# Prototipo_1_2.net
KiCad netlist of a schematic drawn in EAGLE
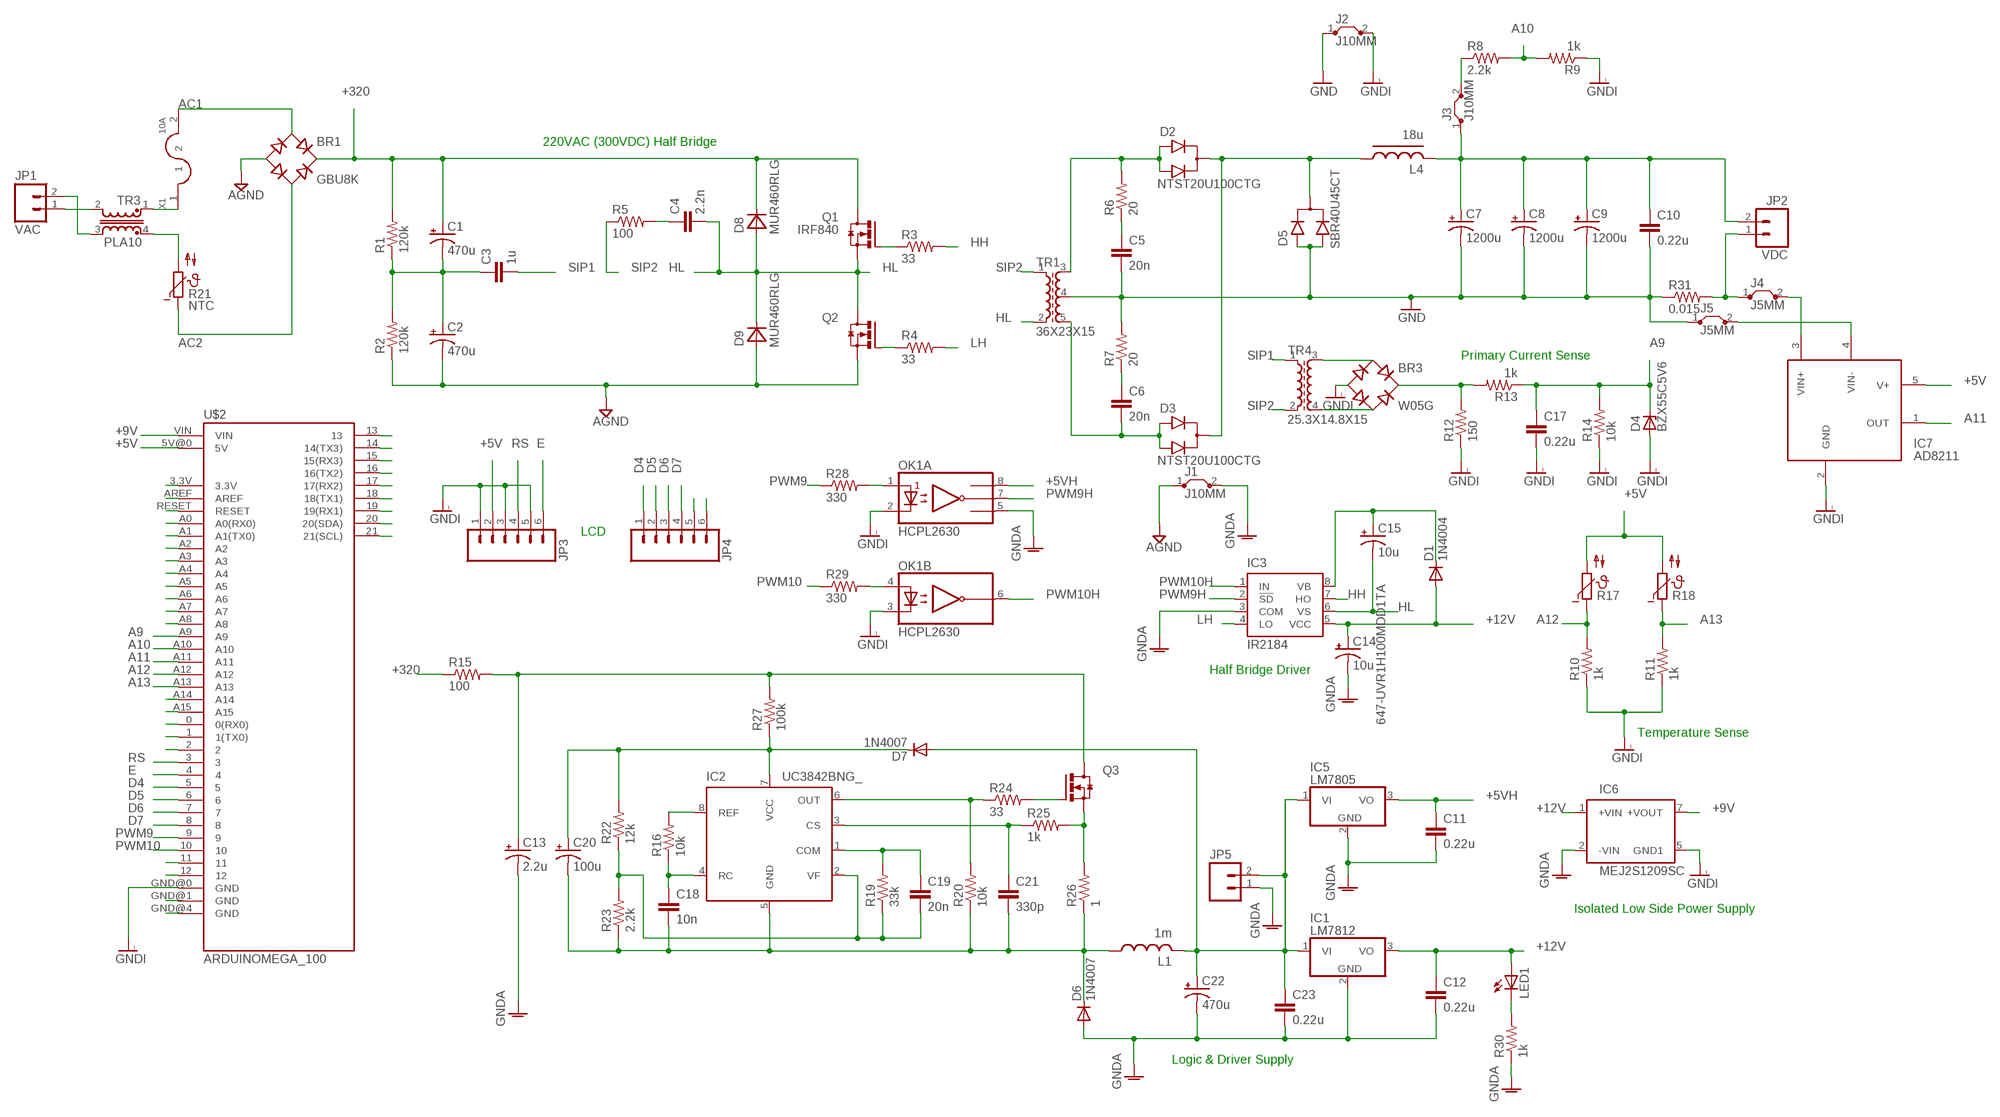
[diagram p0: schematic, sheet 1]

(export (version "E")
  (design (tool "Eeschema 10.0.6"))
  (components
    (comp (ref "BR1")
      (value "GBU8K")
      (footprint "eagle-import:GBU")
      (libsource (lib "eagle-import") (part "GBU8K"))
    )
    (comp (ref "BR3")
      (value "W05G")
      (footprint "eagle-import:WOG")
      (libsource (lib "eagle-import") (part "WG05"))
    )
    (comp (ref "C1")
      (value "470u")
      (footprint "eagle-import:CPOL_RADIAL_470UF_250V")
      (libsource (lib "eagle-import") (part "CAP_470UF_250V"))
    )
    (comp (ref "C2")
      (value "470u")
      (footprint "eagle-import:CPOL_RADIAL_470UF_250V")
      (libsource (lib "eagle-import") (part "CAP_470UF_250V"))
    )
    (comp (ref "C3")
      (value "1u")
      (footprint "eagle-import:C22.5B8")
      (libsource (lib "eagle-import") (part "C22/8"))
    )
    (comp (ref "C4")
      (value "2.2n")
      (footprint "eagle-import:C7.5B4")
      (libsource (lib "eagle-import") (part "C7.5/4"))
    )
    (comp (ref "C5")
      (value "20n")
      (footprint "eagle-import:C10B4")
      (libsource (lib "eagle-import") (part "C10/4"))
    )
    (comp (ref "C6")
      (value "20n")
      (footprint "eagle-import:C10B4")
      (libsource (lib "eagle-import") (part "C10/4"))
    )
    (comp (ref "C7")
      (value "1200u")
      (footprint "eagle-import:CPOL-RADIAL-1000UF-25V")
      (libsource (lib "eagle-import") (part "CAP_POLPTH4"))
    )
    (comp (ref "C8")
      (value "1200u")
      (footprint "eagle-import:CPOL-RADIAL-1000UF-25V")
      (libsource (lib "eagle-import") (part "CAP_POLPTH4"))
    )
    (comp (ref "C9")
      (value "1200u")
      (footprint "eagle-import:CPOL-RADIAL-1000UF-25V")
      (libsource (lib "eagle-import") (part "CAP_POLPTH4"))
    )
    (comp (ref "C10")
      (value "0.22u")
      (footprint "eagle-import:C5B3")
      (libsource (lib "eagle-import") (part "C5/3"))
    )
    (comp (ref "C11")
      (value "0.22u")
      (footprint "eagle-import:C5B3")
      (libsource (lib "eagle-import") (part "C5/3"))
    )
    (comp (ref "C12")
      (value "0.22u")
      (footprint "eagle-import:C5B3")
      (libsource (lib "eagle-import") (part "C5/3"))
    )
    (comp (ref "C13")
      (value "2.2u")
      (footprint "eagle-import:E5-5")
      (libsource (lib "eagle-import") (part "CPOL-USE5-5"))
    )
    (comp (ref "C14")
      (value "10u")
      (footprint "eagle-import:E2,5-6E")
      (fields (field (name "MOUSER") "647-UVR1H100MDD1TA"))
      (libsource (lib "eagle-import") (part "CPOL-USE2,5-6E"))
    )
    (comp (ref "C15")
      (value "10u")
      (footprint "eagle-import:E2,5-6E")
      (libsource (lib "eagle-import") (part "CPOL-USE2,5-6E"))
    )
    (comp (ref "C17")
      (value "0.22u")
      (footprint "eagle-import:C5B3")
      (libsource (lib "eagle-import") (part "C5/3"))
    )
    (comp (ref "C18")
      (value "10n")
      (footprint "eagle-import:C7.5B3")
      (libsource (lib "eagle-import") (part "C7.5/3"))
    )
    (comp (ref "C19")
      (value "20n")
      (footprint "eagle-import:C10B4")
      (libsource (lib "eagle-import") (part "C10/4"))
    )
    (comp (ref "C20")
      (value "100u")
      (footprint "eagle-import:E2,5-7")
      (libsource (lib "eagle-import") (part "CPOL-USE2.5-7"))
    )
    (comp (ref "C21")
      (value "330p")
      (footprint "eagle-import:C7.5B4")
      (libsource (lib "eagle-import") (part "C7.5/4"))
    )
    (comp (ref "C22")
      (value "470u")
      (footprint "eagle-import:E5-8,5")
      (libsource (lib "eagle-import") (part "CPOL-USE5-8.5"))
    )
    (comp (ref "C23")
      (value "0.22u")
      (footprint "eagle-import:C5B3")
      (libsource (lib "eagle-import") (part "C5/3"))
    )
    (comp (ref "D1")
      (value "1N4004")
      (footprint "eagle-import:DO41-10")
      (libsource (lib "eagle-import") (part "1N4004"))
    )
    (comp (ref "D2")
      (value "NTST20U100CTG")
      (footprint "eagle-import:TO220V")
      (libsource (lib "eagle-import") (part "NTST20U100CTG"))
    )
    (comp (ref "D3")
      (value "NTST20U100CTG")
      (footprint "eagle-import:TO220V")
      (libsource (lib "eagle-import") (part "NTST20U100CTG"))
    )
    (comp (ref "D4")
      (value "BZX55C5V6")
      (footprint "eagle-import:DO35Z10")
      (libsource (lib "eagle-import") (part "BZX55"))
    )
    (comp (ref "D5")
      (value "SBR40U45CT")
      (footprint "eagle-import:TO220V")
      (libsource (lib "eagle-import") (part "SBR40U45CT"))
    )
    (comp (ref "D6")
      (value "1N4007")
      (footprint "eagle-import:DO41-10")
      (libsource (lib "eagle-import") (part "1N4004"))
    )
    (comp (ref "D7")
      (value "1N4007")
      (footprint "eagle-import:DO41-10")
      (libsource (lib "eagle-import") (part "1N4004"))
    )
    (comp (ref "D8")
      (value "MUR460RLG")
      (footprint "eagle-import:CB429-17")
      (libsource (lib "eagle-import") (part "MUR460RLG"))
    )
    (comp (ref "D9")
      (value "MUR460RLG")
      (footprint "eagle-import:CB429-17")
      (libsource (lib "eagle-import") (part "MUR460RLG"))
    )
    (comp (ref "IC1")
      (value "LM7812")
      (footprint "eagle-import:TO220V")
      (libsource (lib "eagle-import") (part "78TV8"))
    )
    (comp (ref "IC2")
      (value "UC3842BNG_")
      (footprint "eagle-import:DIL08")
      (libsource (lib "eagle-import") (part "UC3842BNG_"))
    )
    (comp (ref "IC3")
      (value "IR2184")
      (footprint "eagle-import:DIL08")
      (fields (field (name "MF") "INTERNATIONAL RECTIFIER(IR)"))
      (libsource (lib "eagle-import") (part "IR2184"))
    )
    (comp (ref "IC5")
      (value "LM7805")
      (footprint "eagle-import:TO220V")
      (libsource (lib "eagle-import") (part "78TV8"))
    )
    (comp (ref "IC6")
      (value "MEJ2S1209SC")
      (footprint "eagle-import:MEJ2S1209SC")
      (libsource (lib "eagle-import") (part "MEJ2S1209SC"))
    )
    (comp (ref "IC7")
      (value "AD8211")
      (footprint "eagle-import:RJ-5")
      (libsource (lib "eagle-import") (part "AD8211"))
    )
    (comp (ref "J1")
      (value "J10MM")
      (footprint "eagle-import:10")
      (libsource (lib "eagle-import") (part "J10MM"))
    )
    (comp (ref "J2")
      (value "J10MM")
      (footprint "eagle-import:10")
      (libsource (lib "eagle-import") (part "J10MM"))
    )
    (comp (ref "J3")
      (value "J10MM")
      (footprint "eagle-import:10")
      (libsource (lib "eagle-import") (part "J10MM"))
    )
    (comp (ref "J4")
      (value "J5MM")
      (footprint "eagle-import:05")
      (libsource (lib "eagle-import") (part "J5MM"))
    )
    (comp (ref "J5")
      (value "J5MM")
      (footprint "eagle-import:05")
      (libsource (lib "eagle-import") (part "J5MM"))
    )
    (comp (ref "JP1")
      (value "VAC")
      (footprint "eagle-import:SCREWTERMINAL-3.5MM-2")
      (libsource (lib "eagle-import") (part "M023.5MM"))
    )
    (comp (ref "JP2")
      (value "VDC")
      (footprint "eagle-import:SCREWTERMINAL-5MM-2")
      (libsource (lib "eagle-import") (part "M025MM"))
    )
    (comp (ref "JP3")
      (value "M06SIP")
      (footprint "eagle-import:1X06")
      (libsource (lib "eagle-import") (part "M06SIP"))
    )
    (comp (ref "JP4")
      (value "M06SIP")
      (footprint "eagle-import:1X06")
      (libsource (lib "eagle-import") (part "M06SIP"))
    )
    (comp (ref "JP5")
      (value "M02LOCK_LONGPADS")
      (footprint "eagle-import:1X02_LOCK_LONGPADS")
      (libsource (lib "eagle-import") (part "M02LOCK_LONGPADS"))
    )
    (comp (ref "L1")
      (value "1m")
      (footprint "eagle-import:E5-6")
      (libsource (lib "eagle-import") (part "810-TSL0709RA102KR19"))
    )
    (comp (ref "L4")
      (value "18u")
      (footprint "eagle-import:CHOKE_18U")
      (libsource (lib "eagle-import") (part "CHOKE_18U"))
    )
    (comp (ref "LED1")
      (value "LED3MM")
      (footprint "eagle-import:LED3MM")
      (libsource (lib "eagle-import") (part "LED3MM"))
    )
    (comp (ref "OK1")
      (value "HCPL2630")
      (footprint "eagle-import:DIL08")
      (fields (field (name "MF") "AGILENT TECHNOLOGIES") (field (name "MPN") "HCPL-2630-000E"))
      (libsource (lib "eagle-import") (part "HCPL2630"))
    )
    (comp (ref "Q1")
      (value "IRF840")
      (footprint "eagle-import:TO220HV")
      (libsource (lib "eagle-import") (part "IRF840"))
    )
    (comp (ref "Q2")
      (value "IRF840")
      (footprint "eagle-import:TO220HV")
      (libsource (lib "eagle-import") (part "IRF840"))
    )
    (comp (ref "Q3")
      (value "IRF840")
      (footprint "eagle-import:TO220HV")
      (libsource (lib "eagle-import") (part "IRF840"))
    )
    (comp (ref "R1")
      (value "120k")
      (footprint "eagle-import:AXIAL-0.4")
      (libsource (lib "eagle-import") (part "RESISTORPTH-1/4W"))
    )
    (comp (ref "R2")
      (value "120k")
      (footprint "eagle-import:AXIAL-0.4")
      (libsource (lib "eagle-import") (part "RESISTORPTH-1/4W"))
    )
    (comp (ref "R3")
      (value "33")
      (footprint "eagle-import:AXIAL-0.5")
      (libsource (lib "eagle-import") (part "RESISTORPTH-1/2W"))
    )
    (comp (ref "R4")
      (value "33")
      (footprint "eagle-import:AXIAL-0.5")
      (libsource (lib "eagle-import") (part "RESISTORPTH-1/2W"))
    )
    (comp (ref "R5")
      (value "100")
      (footprint "eagle-import:0922V")
      (libsource (lib "eagle-import") (part "R-US_0922V"))
    )
    (comp (ref "R6")
      (value "20")
      (footprint "eagle-import:AXIAL-0.5")
      (libsource (lib "eagle-import") (part "RESISTORPTH-1/2W"))
    )
    (comp (ref "R7")
      (value "20")
      (footprint "eagle-import:AXIAL-0.5")
      (libsource (lib "eagle-import") (part "RESISTORPTH-1/2W"))
    )
    (comp (ref "R8")
      (value "2.2k")
      (footprint "eagle-import:AXIAL-0.4")
      (libsource (lib "eagle-import") (part "RESISTORPTH-1/4W"))
    )
    (comp (ref "R9")
      (value "1k")
      (footprint "eagle-import:AXIAL-0.4")
      (libsource (lib "eagle-import") (part "RESISTORPTH-1/4W"))
    )
    (comp (ref "R10")
      (value "1k")
      (footprint "eagle-import:AXIAL-0.4")
      (libsource (lib "eagle-import") (part "RESISTORPTH-1/4W"))
    )
    (comp (ref "R11")
      (value "1k")
      (footprint "eagle-import:AXIAL-0.4")
      (libsource (lib "eagle-import") (part "RESISTORPTH-1/4W"))
    )
    (comp (ref "R12")
      (value "150")
      (footprint "eagle-import:AXIAL-0.4")
      (libsource (lib "eagle-import") (part "RESISTORPTH-1/4W"))
    )
    (comp (ref "R13")
      (value "1k")
      (footprint "eagle-import:AXIAL-0.4")
      (libsource (lib "eagle-import") (part "RESISTORPTH-1/4W"))
    )
    (comp (ref "R14")
      (value "10k")
      (footprint "eagle-import:AXIAL-0.4")
      (libsource (lib "eagle-import") (part "RESISTORPTH-1/4W"))
    )
    (comp (ref "R15")
      (value "100")
      (footprint "eagle-import:AXIAL-0.4")
      (libsource (lib "eagle-import") (part "RESISTORPTH-1/4W"))
    )
    (comp (ref "R16")
      (value "10k")
      (footprint "eagle-import:AXIAL-0.4")
      (libsource (lib "eagle-import") (part "RESISTORPTH-1/4W"))
    )
    (comp (ref "R17")
      (value "NTC640")
      (footprint "eagle-import:P640")
      (libsource (lib "eagle-import") (part "NTC640"))
    )
    (comp (ref "R18")
      (value "NTC640")
      (footprint "eagle-import:P640")
      (fields (field (name "OC_FARNELL") "unknown") (field (name "OC_NEWARK") "unknown"))
      (libsource (lib "eagle-import") (part "NTC640"))
    )
    (comp (ref "R19")
      (value "33k")
      (footprint "eagle-import:AXIAL-0.4")
      (libsource (lib "eagle-import") (part "RESISTORPTH-1/4W"))
    )
    (comp (ref "R20")
      (value "10k")
      (footprint "eagle-import:AXIAL-0.4")
      (libsource (lib "eagle-import") (part "RESISTORPTH-1/4W"))
    )
    (comp (ref "R21")
      (value "NTC")
      (footprint "eagle-import:C075-042X103")
      (libsource (lib "eagle-import") (part "NTC_5D2-14LD"))
    )
    (comp (ref "R22")
      (value "12k")
      (footprint "eagle-import:AXIAL-0.4")
      (libsource (lib "eagle-import") (part "RESISTORPTH-1/4W"))
    )
    (comp (ref "R23")
      (value "2.2k")
      (footprint "eagle-import:AXIAL-0.4")
      (libsource (lib "eagle-import") (part "RESISTORPTH-1/4W"))
    )
    (comp (ref "R24")
      (value "33")
      (footprint "eagle-import:AXIAL-0.5")
      (libsource (lib "eagle-import") (part "RESISTORPTH-1/2W"))
    )
    (comp (ref "R25")
      (value "1k")
      (footprint "eagle-import:AXIAL-0.4")
      (libsource (lib "eagle-import") (part "RESISTORPTH-1/4W"))
    )
    (comp (ref "R26")
      (value "1")
      (footprint "eagle-import:AXIAL-0.4")
      (libsource (lib "eagle-import") (part "RESISTORPTH-1/4W"))
    )
    (comp (ref "R27")
      (value "100k")
      (footprint "eagle-import:AXIAL-0.4")
      (libsource (lib "eagle-import") (part "RESISTORPTH-1/4W"))
    )
    (comp (ref "R28")
      (value "330")
      (footprint "eagle-import:AXIAL-0.4")
      (libsource (lib "eagle-import") (part "RESISTORPTH-1/4W"))
    )
    (comp (ref "R29")
      (value "330")
      (footprint "eagle-import:AXIAL-0.4")
      (libsource (lib "eagle-import") (part "RESISTORPTH-1/4W"))
    )
    (comp (ref "R30")
      (value "1k")
      (footprint "eagle-import:AXIAL-0.4")
      (libsource (lib "eagle-import") (part "RESISTORPTH-1/4W"))
    )
    (comp (ref "R31")
      (value "0.015")
      (footprint "eagle-import:RSENSE")
      (libsource (lib "eagle-import") (part "RSENSE"))
    )
    (comp (ref "TR1")
      (value "36X23X15")
      (footprint "eagle-import:CORE_36X23X15")
      (libsource (lib "eagle-import") (part "36X23X15_N87"))
    )
    (comp (ref "TR3")
      (value "PLA10")
      (footprint "eagle-import:COMMON_MODE_CHOKE_PLA10")
      (libsource (lib "eagle-import") (part "COMMON_MODE_CHOKE_PLA10"))
    )
    (comp (ref "TR4")
      (value "25.3X14.8X15")
      (footprint "eagle-import:CORE_25.3X14.8X15")
      (libsource (lib "eagle-import") (part "25.3X14.8X15_N87"))
    )
    (comp (ref "U$2")
      (value "ARDUINOMEGA_100")
      (footprint "eagle-import:ARDUINOMEGA_100")
      (libsource (lib "eagle-import") (part "ARDUINOMEGA_100"))
    )
    (comp (ref "X1")
      (value "10A")
      (footprint "eagle-import:FUSE_HOLDER_5X20")
      (libsource (lib "eagle-import") (part "FUSE_HOLDER_5X20"))
    )
  )
  (nets
    (net (code "1") (name "/+5V") (class "Default")
      (node (ref "IC7") (pin "5") (pinfunction "V+_5") (pintype "bidirectional"))
      (node (ref "JP3") (pin "2") (pinfunction "2_2") (pintype "passive"))
      (node (ref "R17") (pin "2") (pinfunction "2_2") (pintype "passive"))
      (node (ref "R18") (pin "2") (pinfunction "2_2") (pintype "passive"))
      (node (ref "U$2") (pin "5V@0") (pinfunction "5V_5V@0") (pintype "bidirectional"))
    )
    (net (code "2") (name "/+5VH") (class "Default")
      (node (ref "C11") (pin "1") (pinfunction "1_1") (pintype "passive"))
      (node (ref "IC5") (pin "3") (pinfunction "VO_3") (pintype "passive"))
      (node (ref "OK1") (pin "8") (pinfunction "VCC_8") (pintype "passive"))
    )
    (net (code "3") (name "/+9V") (class "Default")
      (node (ref "IC6") (pin "7") (pinfunction "+VOUT_7") (pintype "power_in"))
      (node (ref "U$2") (pin "VIN") (pinfunction "VIN_VIN") (pintype "bidirectional"))
    )
    (net (code "4") (name "/+12V") (class "Default")
      (node (ref "C12") (pin "1") (pinfunction "1_1") (pintype "passive"))
      (node (ref "C14") (pin "+") (pinfunction "+_+") (pintype "passive"))
      (node (ref "D1") (pin "A") (pinfunction "A_A") (pintype "passive"))
      (node (ref "IC1") (pin "3") (pinfunction "VO_3") (pintype "passive"))
      (node (ref "IC3") (pin "5") (pinfunction "VCC_5") (pintype "output"))
      (node (ref "IC6") (pin "1") (pinfunction "+VIN_1") (pintype "power_in"))
      (node (ref "LED1") (pin "A") (pinfunction "A_A") (pintype "passive"))
    )
    (net (code "5") (name "/+320") (class "Default")
      (node (ref "BR1") (pin "4") (pinfunction "+_4") (pintype "passive"))
      (node (ref "C1") (pin "1") (pinfunction "+_1") (pintype "passive"))
      (node (ref "D8") (pin "C") (pinfunction "C_C") (pintype "passive"))
      (node (ref "Q1") (pin "2") (pinfunction "D_2") (pintype "passive"))
      (node (ref "R1") (pin "P$2") (pinfunction "2_P$2") (pintype "passive"))
      (node (ref "R15") (pin "P$1") (pinfunction "1_P$1") (pintype "passive"))
    )
    (net (code "6") (name "/A9") (class "Default")
      (node (ref "C17") (pin "1") (pinfunction "1_1") (pintype "passive"))
      (node (ref "D4") (pin "C") (pinfunction "C_C") (pintype "passive"))
      (node (ref "R13") (pin "P$1") (pinfunction "1_P$1") (pintype "passive"))
      (node (ref "R14") (pin "P$2") (pinfunction "2_P$2") (pintype "passive"))
      (node (ref "U$2") (pin "A9") (pinfunction "A9_A9") (pintype "bidirectional"))
    )
    (net (code "7") (name "/A10") (class "Default")
      (node (ref "R8") (pin "P$2") (pinfunction "2_P$2") (pintype "passive"))
      (node (ref "R9") (pin "P$2") (pinfunction "2_P$2") (pintype "passive"))
      (node (ref "U$2") (pin "A10") (pinfunction "A10_A10") (pintype "bidirectional"))
    )
    (net (code "8") (name "/A11") (class "Default")
      (node (ref "IC7") (pin "1") (pinfunction "OUT_1") (pintype "bidirectional"))
      (node (ref "U$2") (pin "A11") (pinfunction "A11_A11") (pintype "bidirectional"))
    )
    (net (code "9") (name "/A12") (class "Default")
      (node (ref "R10") (pin "P$2") (pinfunction "2_P$2") (pintype "passive"))
      (node (ref "R17") (pin "1") (pinfunction "1_1") (pintype "passive"))
      (node (ref "U$2") (pin "A12") (pinfunction "A12_A12") (pintype "bidirectional"))
    )
    (net (code "10") (name "/A13") (class "Default")
      (node (ref "R11") (pin "P$2") (pinfunction "2_P$2") (pintype "passive"))
      (node (ref "R18") (pin "1") (pinfunction "1_1") (pintype "passive"))
      (node (ref "U$2") (pin "A13") (pinfunction "A13_A13") (pintype "bidirectional"))
    )
    (net (code "11") (name "/AC1") (class "Default")
      (node (ref "BR1") (pin "2") (pinfunction "AC1_2") (pintype "passive"))
      (node (ref "X1") (pin "2") (pinfunction "2_2") (pintype "bidirectional"))
    )
    (net (code "12") (name "/AC2") (class "Default")
      (node (ref "BR1") (pin "3") (pinfunction "AC2_3") (pintype "passive"))
      (node (ref "R21") (pin "1") (pinfunction "1_1") (pintype "passive"))
    )
    (net (code "13") (name "/D4") (class "Default")
      (node (ref "JP4") (pin "1") (pinfunction "1_1") (pintype "passive"))
      (node (ref "U$2") (pin "5") (pinfunction "5_5") (pintype "bidirectional"))
    )
    (net (code "14") (name "/D5") (class "Default")
      (node (ref "JP4") (pin "2") (pinfunction "2_2") (pintype "passive"))
      (node (ref "U$2") (pin "6") (pinfunction "6_6") (pintype "bidirectional"))
    )
    (net (code "15") (name "/D6") (class "Default")
      (node (ref "JP4") (pin "3") (pinfunction "3_3") (pintype "passive"))
      (node (ref "U$2") (pin "7") (pinfunction "7_7") (pintype "bidirectional"))
    )
    (net (code "16") (name "/D7") (class "Default")
      (node (ref "JP4") (pin "4") (pinfunction "4_4") (pintype "passive"))
      (node (ref "U$2") (pin "8") (pinfunction "8_8") (pintype "bidirectional"))
    )
    (net (code "17") (name "/E") (class "Default")
      (node (ref "JP3") (pin "6") (pinfunction "6_6") (pintype "passive"))
      (node (ref "U$2") (pin "4") (pinfunction "4_4") (pintype "bidirectional"))
    )
    (net (code "18") (name "/HH") (class "Default")
      (node (ref "IC3") (pin "7") (pinfunction "HO_7") (pintype "passive"))
      (node (ref "R3") (pin "P$2") (pinfunction "2_P$2") (pintype "passive"))
    )
    (net (code "19") (name "/HL") (class "Default")
      (node (ref "C15") (pin "-") (pinfunction "-_-") (pintype "passive"))
      (node (ref "C4") (pin "2") (pinfunction "2_2") (pintype "passive"))
      (node (ref "D8") (pin "A") (pinfunction "A_A") (pintype "passive"))
      (node (ref "D9") (pin "C") (pinfunction "C_C") (pintype "passive"))
      (node (ref "IC3") (pin "6") (pinfunction "VS_6") (pintype "input"))
      (node (ref "Q1") (pin "3") (pinfunction "S_3") (pintype "passive"))
      (node (ref "Q2") (pin "2") (pinfunction "D_2") (pintype "passive"))
      (node (ref "TR1") (pin "2") (pinfunction "2_2") (pintype "passive"))
    )
    (net (code "20") (name "/LH") (class "Default")
      (node (ref "IC3") (pin "4") (pinfunction "LO_4") (pintype "power_in"))
      (node (ref "R4") (pin "P$2") (pinfunction "2_P$2") (pintype "passive"))
    )
    (net (code "21") (name "/PWM9") (class "Default")
      (node (ref "R28") (pin "P$1") (pinfunction "1_P$1") (pintype "passive"))
      (node (ref "U$2") (pin "9") (pinfunction "9_9") (pintype "bidirectional"))
    )
    (net (code "22") (name "/PWM9H") (class "Default")
      (node (ref "IC3") (pin "2") (pinfunction "~{SD}_2") (pintype "input"))
      (node (ref "OK1") (pin "7") (pinfunction "VO1_7") (pintype "passive"))
    )
    (net (code "23") (name "/PWM10") (class "Default")
      (node (ref "R29") (pin "P$1") (pinfunction "1_P$1") (pintype "passive"))
      (node (ref "U$2") (pin "10") (pinfunction "10_10") (pintype "bidirectional"))
    )
    (net (code "24") (name "/PWM10H") (class "Default")
      (node (ref "IC3") (pin "1") (pinfunction "IN_1") (pintype "power_in"))
      (node (ref "OK1") (pin "6") (pinfunction "VO2_6") (pintype "passive"))
    )
    (net (code "25") (name "/RS") (class "Default")
      (node (ref "JP3") (pin "4") (pinfunction "4_4") (pintype "passive"))
      (node (ref "U$2") (pin "3") (pinfunction "3_3") (pintype "bidirectional"))
    )
    (net (code "26") (name "/SIP1") (class "Default")
      (node (ref "C3") (pin "2") (pinfunction "2_2") (pintype "passive"))
      (node (ref "TR4") (pin "1") (pinfunction "1_1") (pintype "passive"))
    )
    (net (code "27") (name "/SIP2") (class "Default")
      (node (ref "R5") (pin "1") (pinfunction "1_1") (pintype "passive"))
      (node (ref "TR1") (pin "1") (pinfunction "1_1") (pintype "passive"))
      (node (ref "TR4") (pin "2") (pinfunction "2_2") (pintype "passive"))
    )
    (net (code "28") (name "AGND") (class "Default")
      (node (ref "BR1") (pin "1") (pinfunction "-_1") (pintype "passive"))
      (node (ref "C2") (pin "2") (pinfunction "-_2") (pintype "passive"))
      (node (ref "D9") (pin "A") (pinfunction "A_A") (pintype "passive"))
      (node (ref "J1") (pin "1") (pinfunction "1_1") (pintype "passive"))
      (node (ref "Q2") (pin "3") (pinfunction "S_3") (pintype "passive"))
      (node (ref "R2") (pin "P$1") (pinfunction "1_P$1") (pintype "passive"))
    )
    (net (code "29") (name "GND") (class "Default")
      (node (ref "C10") (pin "2") (pinfunction "2_2") (pintype "passive"))
      (node (ref "C5") (pin "2") (pinfunction "2_2") (pintype "passive"))
      (node (ref "C7") (pin "2") (pinfunction "-_2") (pintype "passive"))
      (node (ref "C8") (pin "2") (pinfunction "-_2") (pintype "passive"))
      (node (ref "C9") (pin "2") (pinfunction "-_2") (pintype "passive"))
      (node (ref "D5") (pin "1") (pinfunction "A1_1") (pintype "passive"))
      (node (ref "D5") (pin "3") (pinfunction "A2_3") (pintype "passive"))
      (node (ref "J2") (pin "1") (pinfunction "1_1") (pintype "passive"))
      (node (ref "J5") (pin "1") (pinfunction "1_1") (pintype "passive"))
      (node (ref "R31") (pin "P$1") (pinfunction "1_P$1") (pintype "passive"))
      (node (ref "R7") (pin "P$2") (pinfunction "2_P$2") (pintype "passive"))
      (node (ref "TR1") (pin "4") (pinfunction "4_4") (pintype "passive"))
    )
    (net (code "30") (name "GNDA") (class "Default")
      (node (ref "C11") (pin "2") (pinfunction "2_2") (pintype "passive"))
      (node (ref "C12") (pin "2") (pinfunction "2_2") (pintype "passive"))
      (node (ref "C13") (pin "-") (pinfunction "-_-") (pintype "passive"))
      (node (ref "C14") (pin "-") (pinfunction "-_-") (pintype "passive"))
      (node (ref "C22") (pin "-") (pinfunction "-_-") (pintype "passive"))
      (node (ref "C23") (pin "2") (pinfunction "2_2") (pintype "passive"))
      (node (ref "D6") (pin "A") (pinfunction "A_A") (pintype "passive"))
      (node (ref "IC1") (pin "2") (pinfunction "GND_2") (pintype "passive"))
      (node (ref "IC3") (pin "3") (pinfunction "COM_3") (pintype "input"))
      (node (ref "IC5") (pin "2") (pinfunction "GND_2") (pintype "passive"))
      (node (ref "IC6") (pin "2") (pinfunction "-VIN_2") (pintype "power_in"))
      (node (ref "J1") (pin "2") (pinfunction "2_2") (pintype "passive"))
      (node (ref "JP5") (pin "1") (pinfunction "1_1") (pintype "passive"))
      (node (ref "OK1") (pin "5") (pinfunction "GND_5") (pintype "passive"))
      (node (ref "R30") (pin "P$1") (pinfunction "1_P$1") (pintype "passive"))
    )
    (net (code "31") (name "GNDI") (class "Default")
      (node (ref "BR3") (pin "-") (pinfunction "-_-") (pintype "passive"))
      (node (ref "C17") (pin "2") (pinfunction "2_2") (pintype "passive"))
      (node (ref "D4") (pin "A") (pinfunction "A_A") (pintype "passive"))
      (node (ref "IC6") (pin "5") (pinfunction "GND1_5") (pintype "power_in"))
      (node (ref "IC7") (pin "2") (pinfunction "GND_2") (pintype "bidirectional"))
      (node (ref "J2") (pin "2") (pinfunction "2_2") (pintype "passive"))
      (node (ref "JP3") (pin "1") (pinfunction "1_1") (pintype "passive"))
      (node (ref "JP3") (pin "3") (pinfunction "3_3") (pintype "passive"))
      (node (ref "JP3") (pin "5") (pinfunction "5_5") (pintype "passive"))
      (node (ref "OK1") (pin "2") (pinfunction "C1_2") (pintype "passive"))
      (node (ref "OK1") (pin "3") (pinfunction "C2_3") (pintype "passive"))
      (node (ref "R10") (pin "P$1") (pinfunction "1_P$1") (pintype "passive"))
      (node (ref "R11") (pin "P$1") (pinfunction "1_P$1") (pintype "passive"))
      (node (ref "R12") (pin "P$1") (pinfunction "1_P$1") (pintype "passive"))
      (node (ref "R14") (pin "P$1") (pinfunction "1_P$1") (pintype "passive"))
      (node (ref "R9") (pin "P$1") (pinfunction "1_P$1") (pintype "passive"))
      (node (ref "U$2") (pin "GND@0") (pinfunction "GND_GND@0") (pintype "bidirectional"))
    )
    (net (code "32") (name "Net-(BR3-PadAC1)") (class "Default")
      (node (ref "BR3") (pin "AC1") (pinfunction "AC1_AC1") (pintype "passive"))
      (node (ref "TR4") (pin "3") (pinfunction "3_3") (pintype "passive"))
    )
    (net (code "33") (name "Net-(BR3-PadAC2)") (class "Default")
      (node (ref "BR3") (pin "AC2") (pinfunction "AC2_AC2") (pintype "passive"))
      (node (ref "TR4") (pin "4") (pinfunction "4_4") (pintype "passive"))
    )
    (net (code "34") (name "Net-(C1--)") (class "Default")
      (node (ref "C1") (pin "2") (pinfunction "-_2") (pintype "passive"))
      (node (ref "C2") (pin "1") (pinfunction "+_1") (pintype "passive"))
      (node (ref "C3") (pin "1") (pinfunction "1_1") (pintype "passive"))
      (node (ref "R1") (pin "P$1") (pinfunction "1_P$1") (pintype "passive"))
      (node (ref "R2") (pin "P$2") (pinfunction "2_P$2") (pintype "passive"))
    )
    (net (code "35") (name "Net-(C4-Pad1)") (class "Default")
      (node (ref "C4") (pin "1") (pinfunction "1_1") (pintype "passive"))
      (node (ref "R5") (pin "2") (pinfunction "2_2") (pintype "passive"))
    )
    (net (code "36") (name "Net-(C7-+)") (class "Default")
      (node (ref "C10") (pin "1") (pinfunction "1_1") (pintype "passive"))
      (node (ref "C7") (pin "1") (pinfunction "+_1") (pintype "passive"))
      (node (ref "C8") (pin "1") (pinfunction "+_1") (pintype "passive"))
      (node (ref "C9") (pin "1") (pinfunction "+_1") (pintype "passive"))
      (node (ref "J3") (pin "1") (pinfunction "1_1") (pintype "passive"))
      (node (ref "JP2") (pin "2") (pinfunction "2_2") (pintype "passive"))
      (node (ref "L4") (pin "2") (pinfunction "2_2") (pintype "passive"))
    )
    (net (code "37") (name "Net-(D2-A1)") (class "Default")
      (node (ref "D2") (pin "1") (pinfunction "A1_1") (pintype "passive"))
      (node (ref "D2") (pin "3") (pinfunction "A2_3") (pintype "passive"))
      (node (ref "R6") (pin "P$2") (pinfunction "2_P$2") (pintype "passive"))
      (node (ref "TR1") (pin "3") (pinfunction "3_3") (pintype "passive"))
    )
    (net (code "38") (name "Net-(D2-C)") (class "Default")
      (node (ref "D2") (pin "2") (pinfunction "C_2") (pintype "passive"))
      (node (ref "D3") (pin "2") (pinfunction "C_2") (pintype "passive"))
      (node (ref "D5") (pin "2") (pinfunction "C_2") (pintype "passive"))
      (node (ref "L4") (pin "1") (pinfunction "1_1") (pintype "passive"))
    )
    (net (code "39") (name "Net-(D3-A1)") (class "Default")
      (node (ref "C6") (pin "2") (pinfunction "2_2") (pintype "passive"))
      (node (ref "D3") (pin "1") (pinfunction "A1_1") (pintype "passive"))
      (node (ref "D3") (pin "3") (pinfunction "A2_3") (pintype "passive"))
      (node (ref "TR1") (pin "5") (pinfunction "5_5") (pintype "passive"))
    )
    (net (code "40") (name "Net-(IC1-VI)") (class "Default")
      (node (ref "C22") (pin "+") (pinfunction "+_+") (pintype "passive"))
      (node (ref "C23") (pin "1") (pinfunction "1_1") (pintype "passive"))
      (node (ref "D7") (pin "A") (pinfunction "A_A") (pintype "passive"))
      (node (ref "IC1") (pin "1") (pinfunction "VI_1") (pintype "input"))
      (node (ref "IC5") (pin "1") (pinfunction "VI_1") (pintype "input"))
      (node (ref "JP5") (pin "2") (pinfunction "2_2") (pintype "passive"))
      (node (ref "L1") (pin "-") (pinfunction "2_-") (pintype "passive"))
    )
    (net (code "41") (name "Net-(IC2-COM)") (class "Default")
      (node (ref "C19") (pin "1") (pinfunction "1_1") (pintype "passive"))
      (node (ref "IC2") (pin "1") (pinfunction "COM_1") (pintype "bidirectional"))
      (node (ref "R19") (pin "P$2") (pinfunction "2_P$2") (pintype "passive"))
    )
    (net (code "42") (name "Net-(IC2-CS)") (class "Default")
      (node (ref "C21") (pin "1") (pinfunction "1_1") (pintype "passive"))
      (node (ref "IC2") (pin "3") (pinfunction "CS_3") (pintype "bidirectional"))
      (node (ref "R25") (pin "P$1") (pinfunction "1_P$1") (pintype "passive"))
    )
    (net (code "43") (name "Net-(IC2-GND)") (class "Default")
      (node (ref "C18") (pin "2") (pinfunction "2_2") (pintype "passive"))
      (node (ref "C20") (pin "-") (pinfunction "-_-") (pintype "passive"))
      (node (ref "C21") (pin "2") (pinfunction "2_2") (pintype "passive"))
      (node (ref "D6") (pin "C") (pinfunction "C_C") (pintype "passive"))
      (node (ref "IC2") (pin "5") (pinfunction "GND_5") (pintype "bidirectional"))
      (node (ref "L1") (pin "+") (pinfunction "1_+") (pintype "passive"))
      (node (ref "R20") (pin "P$1") (pinfunction "1_P$1") (pintype "passive"))
      (node (ref "R23") (pin "P$1") (pinfunction "1_P$1") (pintype "passive"))
      (node (ref "R26") (pin "P$1") (pinfunction "1_P$1") (pintype "passive"))
    )
    (net (code "44") (name "Net-(IC2-OUT)") (class "Default")
      (node (ref "IC2") (pin "6") (pinfunction "OUT_6") (pintype "bidirectional"))
      (node (ref "R20") (pin "P$2") (pinfunction "2_P$2") (pintype "passive"))
      (node (ref "R24") (pin "P$1") (pinfunction "1_P$1") (pintype "passive"))
    )
    (net (code "45") (name "Net-(IC2-RC)") (class "Default")
      (node (ref "C18") (pin "1") (pinfunction "1_1") (pintype "passive"))
      (node (ref "IC2") (pin "4") (pinfunction "RC_4") (pintype "bidirectional"))
      (node (ref "R16") (pin "P$1") (pinfunction "1_P$1") (pintype "passive"))
    )
    (net (code "46") (name "Net-(IC2-REF)") (class "Default")
      (node (ref "IC2") (pin "8") (pinfunction "REF_8") (pintype "bidirectional"))
      (node (ref "R16") (pin "P$2") (pinfunction "2_P$2") (pintype "passive"))
    )
    (net (code "47") (name "Net-(IC2-VCC)") (class "Default")
      (node (ref "C20") (pin "+") (pinfunction "+_+") (pintype "passive"))
      (node (ref "D7") (pin "C") (pinfunction "C_C") (pintype "passive"))
      (node (ref "IC2") (pin "7") (pinfunction "VCC_7") (pintype "bidirectional"))
      (node (ref "R22") (pin "P$2") (pinfunction "2_P$2") (pintype "passive"))
      (node (ref "R27") (pin "P$1") (pinfunction "1_P$1") (pintype "passive"))
    )
    (net (code "48") (name "Net-(IC2-VF)") (class "Default")
      (node (ref "C19") (pin "2") (pinfunction "2_2") (pintype "passive"))
      (node (ref "IC2") (pin "2") (pinfunction "VF_2") (pintype "bidirectional"))
      (node (ref "R19") (pin "P$1") (pinfunction "1_P$1") (pintype "passive"))
      (node (ref "R22") (pin "P$1") (pinfunction "1_P$1") (pintype "passive"))
      (node (ref "R23") (pin "P$2") (pinfunction "2_P$2") (pintype "passive"))
    )
    (net (code "49") (name "Net-(IC3-VB)") (class "Default")
      (node (ref "C15") (pin "+") (pinfunction "+_+") (pintype "passive"))
      (node (ref "D1") (pin "C") (pinfunction "C_C") (pintype "passive"))
      (node (ref "IC3") (pin "8") (pinfunction "VB_8") (pintype "output"))
    )
    (net (code "50") (name "Net-(IC7-VIN+)") (class "Default")
      (node (ref "IC7") (pin "3") (pinfunction "VIN+_3") (pintype "bidirectional"))
      (node (ref "J4") (pin "2") (pinfunction "2_2") (pintype "passive"))
    )
    (net (code "51") (name "Net-(IC7-VIN-)") (class "Default")
      (node (ref "IC7") (pin "4") (pinfunction "VIN-_4") (pintype "bidirectional"))
      (node (ref "J5") (pin "2") (pinfunction "2_2") (pintype "passive"))
    )
    (net (code "52") (name "Net-(JP1-Pad1)") (class "Default")
      (node (ref "JP1") (pin "1") (pinfunction "1_1") (pintype "passive"))
      (node (ref "TR3") (pin "2") (pinfunction "2_2") (pintype "passive"))
    )
    (net (code "53") (name "Net-(JP1-Pad2)") (class "Default")
      (node (ref "JP1") (pin "2") (pinfunction "2_2") (pintype "passive"))
      (node (ref "TR3") (pin "3") (pinfunction "3_3") (pintype "passive"))
    )
    (net (code "54") (name "Net-(LED1-C)") (class "Default")
      (node (ref "LED1") (pin "K") (pinfunction "C_K") (pintype "passive"))
      (node (ref "R30") (pin "P$2") (pinfunction "2_P$2") (pintype "passive"))
    )
    (net (code "55") (name "Net-(OK1A-A1)") (class "Default")
      (node (ref "OK1") (pin "1") (pinfunction "A1_1") (pintype "passive"))
      (node (ref "R28") (pin "P$2") (pinfunction "2_P$2") (pintype "passive"))
    )
    (net (code "56") (name "Net-(OK1B-A2)") (class "Default")
      (node (ref "OK1") (pin "4") (pinfunction "A2_4") (pintype "passive"))
      (node (ref "R29") (pin "P$2") (pinfunction "2_P$2") (pintype "passive"))
    )
    (net (code "57") (name "Net-(Q1-G)") (class "Default")
      (node (ref "Q1") (pin "1") (pinfunction "G_1") (pintype "passive"))
      (node (ref "R3") (pin "P$1") (pinfunction "1_P$1") (pintype "passive"))
    )
    (net (code "58") (name "Net-(Q2-G)") (class "Default")
      (node (ref "Q2") (pin "1") (pinfunction "G_1") (pintype "passive"))
      (node (ref "R4") (pin "P$1") (pinfunction "1_P$1") (pintype "passive"))
    )
    (net (code "59") (name "Net-(Q3-D)") (class "Default")
      (node (ref "C13") (pin "+") (pinfunction "+_+") (pintype "passive"))
      (node (ref "Q3") (pin "2") (pinfunction "D_2") (pintype "passive"))
      (node (ref "R15") (pin "P$2") (pinfunction "2_P$2") (pintype "passive"))
      (node (ref "R27") (pin "P$2") (pinfunction "2_P$2") (pintype "passive"))
    )
    (net (code "60") (name "Net-(Q3-G)") (class "Default")
      (node (ref "Q3") (pin "1") (pinfunction "G_1") (pintype "passive"))
      (node (ref "R24") (pin "P$2") (pinfunction "2_P$2") (pintype "passive"))
    )
    (net (code "61") (name "Net-(Q3-S)") (class "Default")
      (node (ref "Q3") (pin "3") (pinfunction "S_3") (pintype "passive"))
      (node (ref "R25") (pin "P$2") (pinfunction "2_P$2") (pintype "passive"))
      (node (ref "R26") (pin "P$2") (pinfunction "2_P$2") (pintype "passive"))
    )
    (net (code "62") (name "Net-(R6-1)") (class "Default")
      (node (ref "C5") (pin "1") (pinfunction "1_1") (pintype "passive"))
      (node (ref "R6") (pin "P$1") (pinfunction "1_P$1") (pintype "passive"))
    )
    (net (code "63") (name "Net-(R7-1)") (class "Default")
      (node (ref "C6") (pin "1") (pinfunction "1_1") (pintype "passive"))
      (node (ref "R7") (pin "P$1") (pinfunction "1_P$1") (pintype "passive"))
    )
    (net (code "64") (name "Net-(R8-1)") (class "Default")
      (node (ref "J3") (pin "2") (pinfunction "2_2") (pintype "passive"))
      (node (ref "R8") (pin "P$1") (pinfunction "1_P$1") (pintype "passive"))
    )
    (net (code "65") (name "Net-(R12-2)") (class "Default")
      (node (ref "BR3") (pin "+") (pinfunction "+_+") (pintype "passive"))
      (node (ref "R12") (pin "P$2") (pinfunction "2_P$2") (pintype "passive"))
      (node (ref "R13") (pin "P$2") (pinfunction "2_P$2") (pintype "passive"))
    )
    (net (code "66") (name "Net-(R21-Pad2)") (class "Default")
      (node (ref "R21") (pin "2") (pinfunction "2_2") (pintype "passive"))
      (node (ref "TR3") (pin "4") (pinfunction "4_4") (pintype "passive"))
    )
    (net (code "67") (name "Net-(R31-2)") (class "Default")
      (node (ref "J4") (pin "1") (pinfunction "1_1") (pintype "passive"))
      (node (ref "JP2") (pin "1") (pinfunction "1_1") (pintype "passive"))
      (node (ref "R31") (pin "P$2") (pinfunction "2_P$2") (pintype "passive"))
    )
    (net (code "68") (name "Net-(TR3-Pad1)") (class "Default")
      (node (ref "TR3") (pin "1") (pinfunction "1_1") (pintype "passive"))
      (node (ref "X1") (pin "1") (pinfunction "1_1") (pintype "bidirectional"))
    )
    (net (code "69") (name "unconnected-(JP4-Pad5)") (class "Default")
      (node (ref "JP4") (pin "5") (pinfunction "5_5") (pintype "passive"))
    )
    (net (code "70") (name "unconnected-(JP4-Pad6)") (class "Default")
      (node (ref "JP4") (pin "6") (pinfunction "6_6") (pintype "passive"))
    )
    (net (code "71") (name "unconnected-(U$2-0(RX0)-Pad0)") (class "Default")
      (node (ref "U$2") (pin "0") (pinfunction "0(RX0)_0") (pintype "bidirectional"))
    )
    (net (code "72") (name "unconnected-(U$2-1(TX0)-Pad1)") (class "Default")
      (node (ref "U$2") (pin "1") (pinfunction "1(TX0)_1") (pintype "bidirectional"))
    )
    (net (code "73") (name "unconnected-(U$2-14(TX3)-Pad14)") (class "Default")
      (node (ref "U$2") (pin "14") (pinfunction "14(TX3)_14") (pintype "bidirectional"))
    )
    (net (code "74") (name "unconnected-(U$2-15(RX3)-Pad15)") (class "Default")
      (node (ref "U$2") (pin "15") (pinfunction "15(RX3)_15") (pintype "bidirectional"))
    )
    (net (code "75") (name "unconnected-(U$2-16(TX2)-Pad16)") (class "Default")
      (node (ref "U$2") (pin "16") (pinfunction "16(TX2)_16") (pintype "bidirectional"))
    )
    (net (code "76") (name "unconnected-(U$2-17(RX2)-Pad17)") (class "Default")
      (node (ref "U$2") (pin "17") (pinfunction "17(RX2)_17") (pintype "bidirectional"))
    )
    (net (code "77") (name "unconnected-(U$2-18(TX1)-Pad18)") (class "Default")
      (node (ref "U$2") (pin "18") (pinfunction "18(TX1)_18") (pintype "bidirectional"))
    )
    (net (code "78") (name "unconnected-(U$2-19(RX1)-Pad19)") (class "Default")
      (node (ref "U$2") (pin "19") (pinfunction "19(RX1)_19") (pintype "bidirectional"))
    )
    (net (code "79") (name "unconnected-(U$2-20(SDA)-Pad20)") (class "Default")
      (node (ref "U$2") (pin "20") (pinfunction "20(SDA)_20") (pintype "bidirectional"))
    )
    (net (code "80") (name "unconnected-(U$2-21(SCL)-Pad21)") (class "Default")
      (node (ref "U$2") (pin "21") (pinfunction "21(SCL)_21") (pintype "bidirectional"))
    )
    (net (code "81") (name "unconnected-(U$2-A0(RX0)-PadA0)") (class "Default")
      (node (ref "U$2") (pin "A0") (pinfunction "A0(RX0)_A0") (pintype "bidirectional"))
    )
    (net (code "82") (name "unconnected-(U$2-A1(TX0)-PadA1)") (class "Default")
      (node (ref "U$2") (pin "A1") (pinfunction "A1(TX0)_A1") (pintype "bidirectional"))
    )
    (net (code "83") (name "unconnected-(U$2-GND-PadGND@1)") (class "Default")
      (node (ref "U$2") (pin "GND@1") (pinfunction "GND_GND@1") (pintype "bidirectional"))
    )
    (net (code "84") (name "unconnected-(U$2-GND-PadGND@4)") (class "Default")
      (node (ref "U$2") (pin "GND@4") (pinfunction "GND_GND@4") (pintype "bidirectional"))
    )
    (net (code "85") (name "unconnected-(U$2-Pad2)") (class "Default")
      (node (ref "U$2") (pin "2") (pinfunction "2_2") (pintype "bidirectional"))
    )
    (net (code "86") (name "unconnected-(U$2-Pad3.3V)") (class "Default")
      (node (ref "U$2") (pin "3.3V") (pinfunction "3.3V_3.3V") (pintype "bidirectional"))
    )
    (net (code "87") (name "unconnected-(U$2-Pad11)") (class "Default")
      (node (ref "U$2") (pin "11") (pinfunction "11_11") (pintype "bidirectional"))
    )
    (net (code "88") (name "unconnected-(U$2-Pad12)") (class "Default")
      (node (ref "U$2") (pin "12") (pinfunction "12_12") (pintype "bidirectional"))
    )
    (net (code "89") (name "unconnected-(U$2-Pad13)") (class "Default")
      (node (ref "U$2") (pin "13") (pinfunction "13_13") (pintype "bidirectional"))
    )
    (net (code "90") (name "unconnected-(U$2-PadA2)") (class "Default")
      (node (ref "U$2") (pin "A2") (pinfunction "A2_A2") (pintype "bidirectional"))
    )
    (net (code "91") (name "unconnected-(U$2-PadA3)") (class "Default")
      (node (ref "U$2") (pin "A3") (pinfunction "A3_A3") (pintype "bidirectional"))
    )
    (net (code "92") (name "unconnected-(U$2-PadA4)") (class "Default")
      (node (ref "U$2") (pin "A4") (pinfunction "A4_A4") (pintype "bidirectional"))
    )
    (net (code "93") (name "unconnected-(U$2-PadA5)") (class "Default")
      (node (ref "U$2") (pin "A5") (pinfunction "A5_A5") (pintype "bidirectional"))
    )
    (net (code "94") (name "unconnected-(U$2-PadA6)") (class "Default")
      (node (ref "U$2") (pin "A6") (pinfunction "A6_A6") (pintype "bidirectional"))
    )
    (net (code "95") (name "unconnected-(U$2-PadA7)") (class "Default")
      (node (ref "U$2") (pin "A7") (pinfunction "A7_A7") (pintype "bidirectional"))
    )
    (net (code "96") (name "unconnected-(U$2-PadA8)") (class "Default")
      (node (ref "U$2") (pin "A8") (pinfunction "A8_A8") (pintype "bidirectional"))
    )
    (net (code "97") (name "unconnected-(U$2-PadA14)") (class "Default")
      (node (ref "U$2") (pin "A14") (pinfunction "A14_A14") (pintype "bidirectional"))
    )
    (net (code "98") (name "unconnected-(U$2-PadA15)") (class "Default")
      (node (ref "U$2") (pin "A15") (pinfunction "A15_A15") (pintype "bidirectional"))
    )
    (net (code "99") (name "unconnected-(U$2-PadAREF)") (class "Default")
      (node (ref "U$2") (pin "AREF") (pinfunction "AREF_AREF") (pintype "bidirectional"))
    )
    (net (code "100") (name "unconnected-(U$2-PadRESET)") (class "Default")
      (node (ref "U$2") (pin "RESET") (pinfunction "RESET_RESET") (pintype "bidirectional"))
    )
  )
)
